# Power_BAT.net
KiCad netlist of a schematic drawn in Altium Designer
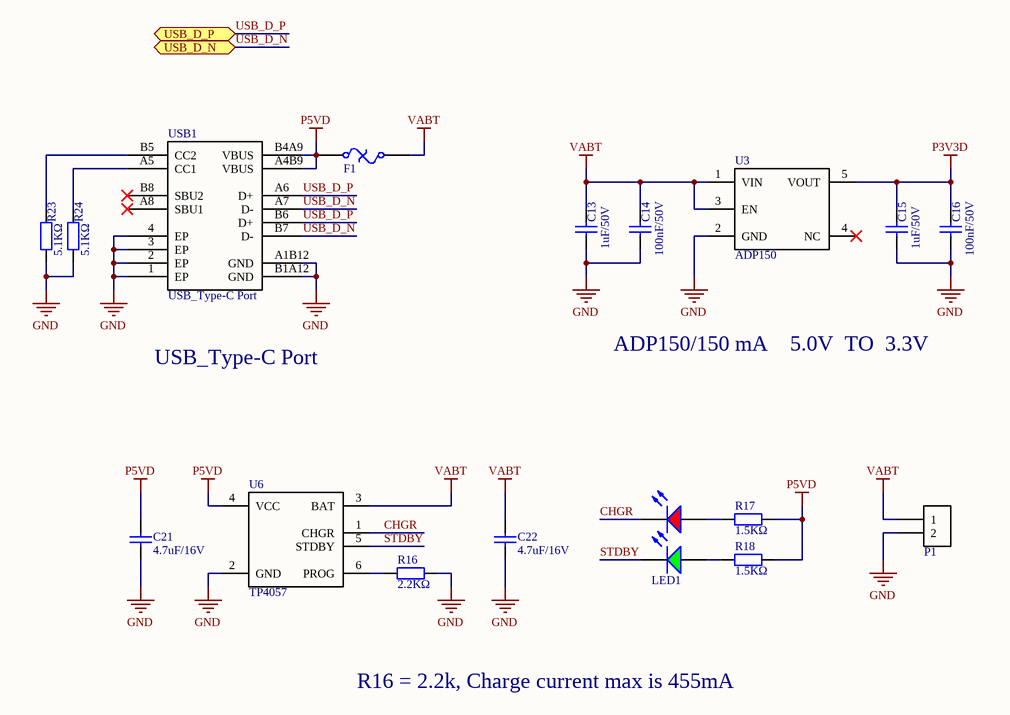
[diagram p0: Power&BAT.SchDoc]

(export (version "E")
  (design (tool "Eeschema 10.0.6"))
  (components
    (comp (ref "C13")
      (value "1uF/50V")
      (footprint "0603_C")
      (description "贴片电容")
      (libsource (lib "Miscellaneous Devices LC") (part "0603 1uF (105) 10% 50V"))
    )
    (comp (ref "C14")
      (value "100nF/50V")
      (footprint "0603_C")
      (description "贴片电容")
      (libsource (lib "Miscellaneous Devices LC") (part "0603 100nF (104) 10% 50V"))
    )
    (comp (ref "C15")
      (value "1uF/50V")
      (footprint "0603_C")
      (description "贴片电容")
      (libsource (lib "Miscellaneous Devices LC") (part "0603 1uF (105) 10% 50V"))
    )
    (comp (ref "C16")
      (value "100nF/50V")
      (footprint "0603_C")
      (description "贴片电容")
      (libsource (lib "Miscellaneous Devices LC") (part "0603 100nF (104) 10% 50V"))
    )
    (comp (ref "C21")
      (value "4.7uF/16V")
      (footprint "0603_C")
      (description "贴片电容")
      (libsource (lib "Miscellaneous Devices LC") (part "0603 4.7uF (475) 10% 16V"))
    )
    (comp (ref "C22")
      (value "4.7uF/16V")
      (footprint "0603_C")
      (description "贴片电容")
      (libsource (lib "Miscellaneous Devices LC") (part "0603 4.7uF (475) 10% 16V"))
    )
    (comp (ref "F1")
      (value "500mA")
      (footprint "F1206")
      (description "Fuse")
      (libsource (lib "Discrete") (part "Fuse"))
    )
    (comp (ref "LED1")
      (value "LTST-C195TGKRKT")
      (footprint "LED_SMD")
      (libsource (lib "Discrete") (part "LED_SMD"))
    )
    (comp (ref "P1")
      (value "Header 2")
      (footprint "1.25_SMD")
      (description "Header, 2-Pin")
      (libsource (lib "Connectors") (part "Header 2"))
    )
    (comp (ref "R16")
      (value "2.2KΩ")
      (footprint "0402_R")
      (description "贴片电阻")
      (libsource (lib "Miscellaneous Devices LC") (part "0402 2.2KΩ (2201) 1%"))
    )
    (comp (ref "R17")
      (value "1.5KΩ")
      (footprint "0402_R")
      (description "贴片电阻")
      (libsource (lib "Miscellaneous Devices LC") (part "0402 1.5KΩ (1501) 1%"))
    )
    (comp (ref "R18")
      (value "1.5KΩ")
      (footprint "0402_R")
      (description "贴片电阻")
      (libsource (lib "Miscellaneous Devices LC") (part "0402 1.5KΩ (1501) 1%"))
    )
    (comp (ref "R23")
      (value "5.1KΩ")
      (footprint "0402_R")
      (description "贴片电阻")
      (libsource (lib "Miscellaneous Devices LC") (part "0402 5.1KΩ (5101) 1%"))
    )
    (comp (ref "R24")
      (value "5.1KΩ")
      (footprint "0402_R")
      (description "贴片电阻")
      (libsource (lib "Miscellaneous Devices LC") (part "0402 5.1KΩ (5101) 1%"))
    )
    (comp (ref "U3")
      (value "ADP150")
      (footprint "SOT23-5")
      (description "Ultralow Noise, 150 mA CMOS Linear Regulator")
      (libsource (lib "IC") (part "ADP150"))
    )
    (comp (ref "U6")
      (value "TP4057")
      (footprint "SOT23-6")
      (description "500mA线性锂离子电池充电器")
      (libsource (lib "IC") (part "TP4057"))
    )
    (comp (ref "USB1")
      (value "USB_Type-C Port")
      (footprint "USB Type C Port (SMD)_16Pin")
      (libsource (lib "Connectors") (part "USB_Type-C Port"))
    )
  )
  (nets
    (net (code "1") (name "/CHGR") (class "Default")
      (node (ref "LED1") (pin "4") (pinfunction "4_4") (pintype "passive"))
      (node (ref "U6") (pin "1") (pinfunction "CHGR_1") (pintype "passive"))
    )
    (net (code "2") (name "/STDBY") (class "Default")
      (node (ref "LED1") (pin "3") (pinfunction "3_3") (pintype "passive"))
      (node (ref "U6") (pin "5") (pinfunction "STDBY_5") (pintype "passive"))
    )
    (net (code "3") (name "/USB_D_N") (class "Default")
      (node (ref "USB1") (pin "A7") (pinfunction "D-_A7") (pintype "passive"))
      (node (ref "USB1") (pin "B7") (pinfunction "D-_B7") (pintype "passive"))
    )
    (net (code "4") (name "/USB_D_P") (class "Default")
      (node (ref "USB1") (pin "A6") (pinfunction "D+_A6") (pintype "passive"))
      (node (ref "USB1") (pin "B6") (pinfunction "D+_B6") (pintype "passive"))
    )
    (net (code "5") (name "GND") (class "Default")
      (node (ref "C13") (pin "1") (pinfunction "1_1") (pintype "passive"))
      (node (ref "C14") (pin "1") (pinfunction "1_1") (pintype "passive"))
      (node (ref "C15") (pin "1") (pinfunction "1_1") (pintype "passive"))
      (node (ref "C16") (pin "1") (pinfunction "1_1") (pintype "passive"))
      (node (ref "C21") (pin "1") (pinfunction "1_1") (pintype "passive"))
      (node (ref "C22") (pin "1") (pinfunction "1_1") (pintype "passive"))
      (node (ref "P1") (pin "2") (pinfunction "2_2") (pintype "passive"))
      (node (ref "R16") (pin "2") (pinfunction "2_2") (pintype "passive"))
      (node (ref "R23") (pin "1") (pinfunction "1_1") (pintype "passive"))
      (node (ref "R24") (pin "1") (pinfunction "1_1") (pintype "passive"))
      (node (ref "U3") (pin "2") (pinfunction "GND_2") (pintype "passive"))
      (node (ref "U6") (pin "2") (pinfunction "GND_2") (pintype "passive"))
      (node (ref "USB1") (pin "1") (pinfunction "EP_1") (pintype "passive"))
      (node (ref "USB1") (pin "2") (pinfunction "EP_2") (pintype "passive"))
      (node (ref "USB1") (pin "3") (pinfunction "EP_3") (pintype "passive"))
      (node (ref "USB1") (pin "4") (pinfunction "EP_4") (pintype "passive"))
      (node (ref "USB1") (pin "A1B12") (pinfunction "GND_A1B12") (pintype "passive"))
      (node (ref "USB1") (pin "B1A12") (pinfunction "GND_B1A12") (pintype "passive"))
    )
    (net (code "6") (name "Net-(LED1-Pad1)") (class "Default")
      (node (ref "LED1") (pin "1") (pinfunction "1_1") (pintype "passive"))
      (node (ref "R18") (pin "1") (pinfunction "1_1") (pintype "passive"))
    )
    (net (code "7") (name "Net-(LED1-Pad2)") (class "Default")
      (node (ref "LED1") (pin "2") (pinfunction "2_2") (pintype "passive"))
      (node (ref "R17") (pin "1") (pinfunction "1_1") (pintype "passive"))
    )
    (net (code "8") (name "Net-(U6-PROG)") (class "Default")
      (node (ref "R16") (pin "1") (pinfunction "1_1") (pintype "passive"))
      (node (ref "U6") (pin "6") (pinfunction "PROG_6") (pintype "passive"))
    )
    (net (code "9") (name "Net-(USB1-CC1)") (class "Default")
      (node (ref "R24") (pin "2") (pinfunction "2_2") (pintype "passive"))
      (node (ref "USB1") (pin "A5") (pinfunction "CC1_A5") (pintype "passive"))
    )
    (net (code "10") (name "Net-(USB1-CC2)") (class "Default")
      (node (ref "R23") (pin "2") (pinfunction "2_2") (pintype "passive"))
      (node (ref "USB1") (pin "B5") (pinfunction "CC2_B5") (pintype "passive"))
    )
    (net (code "11") (name "P3V3D") (class "Default")
      (node (ref "C15") (pin "2") (pinfunction "2_2") (pintype "passive"))
      (node (ref "C16") (pin "2") (pinfunction "2_2") (pintype "passive"))
      (node (ref "U3") (pin "5") (pinfunction "VOUT_5") (pintype "passive"))
    )
    (net (code "12") (name "P5VD") (class "Default")
      (node (ref "C21") (pin "2") (pinfunction "2_2") (pintype "passive"))
      (node (ref "F1") (pin "1") (pinfunction "1_1") (pintype "passive"))
      (node (ref "R17") (pin "2") (pinfunction "2_2") (pintype "passive"))
      (node (ref "R18") (pin "2") (pinfunction "2_2") (pintype "passive"))
      (node (ref "U6") (pin "4") (pinfunction "VCC_4") (pintype "passive"))
      (node (ref "USB1") (pin "A4B9") (pinfunction "VBUS_A4B9") (pintype "passive"))
      (node (ref "USB1") (pin "B4A9") (pinfunction "VBUS_B4A9") (pintype "passive"))
    )
    (net (code "13") (name "VABT") (class "Default")
      (node (ref "C13") (pin "2") (pinfunction "2_2") (pintype "passive"))
      (node (ref "C14") (pin "2") (pinfunction "2_2") (pintype "passive"))
      (node (ref "C22") (pin "2") (pinfunction "2_2") (pintype "passive"))
      (node (ref "F1") (pin "2") (pinfunction "2_2") (pintype "passive"))
      (node (ref "P1") (pin "1") (pinfunction "1_1") (pintype "passive"))
      (node (ref "U3") (pin "1") (pinfunction "VIN_1") (pintype "passive"))
      (node (ref "U3") (pin "3") (pinfunction "EN_3") (pintype "passive"))
      (node (ref "U6") (pin "3") (pinfunction "BAT_3") (pintype "passive"))
    )
    (net (code "14") (name "unconnected-(U3-NC-Pad4)") (class "Default")
      (node (ref "U3") (pin "4") (pinfunction "NC_4") (pintype "passive+no_connect"))
    )
    (net (code "15") (name "unconnected-(USB1-SBU1-PadA8)") (class "Default")
      (node (ref "USB1") (pin "A8") (pinfunction "SBU1_A8") (pintype "passive+no_connect"))
    )
    (net (code "16") (name "unconnected-(USB1-SBU2-PadB8)") (class "Default")
      (node (ref "USB1") (pin "B8") (pinfunction "SBU2_B8") (pintype "passive+no_connect"))
    )
  )
)
